# vreg.net
KiCad netlist of a schematic drawn in Altium Designer
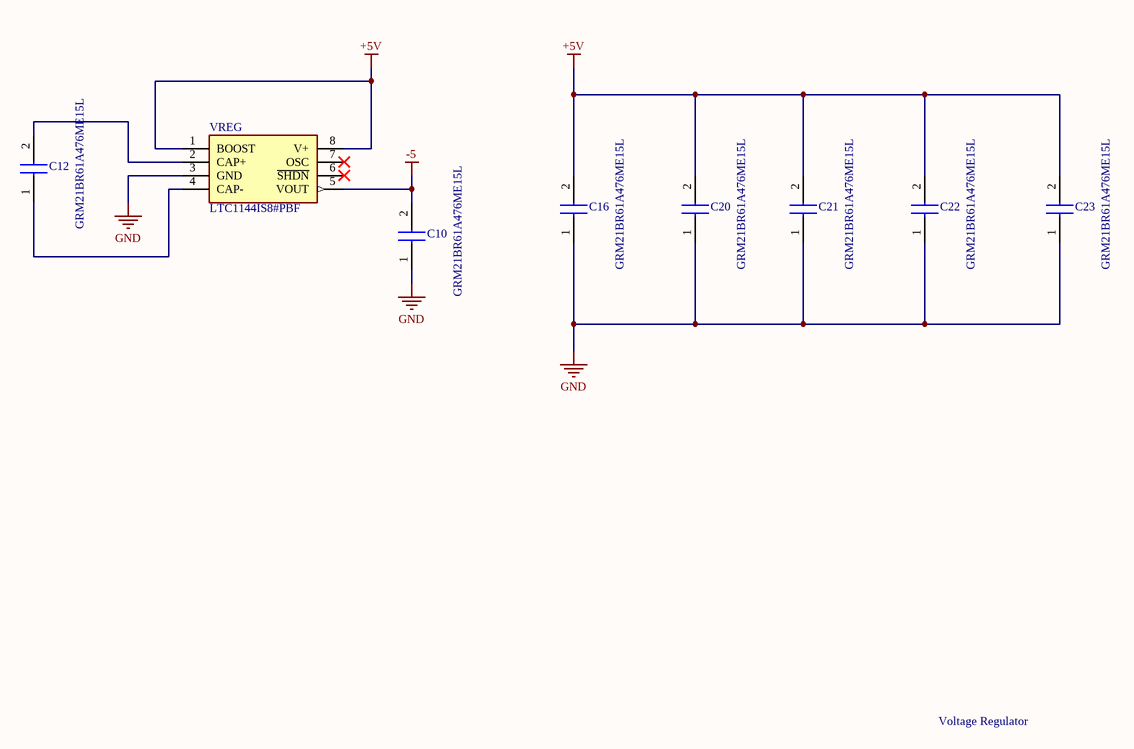
[diagram p0: vreg.SchDoc]

(export (version "E")
  (design (tool "Eeschema 10.0.6"))
  (components
    (comp (ref "C10")
      (value "GRM21BR61A476ME15L")
      (footprint "SamacSys:CAPC2012X145N")
      (description "Capacitor")
      (fields (field (name "MOUSER PART NUMBER") "81-GRM21BR61A476ME5L"))
      (libsource (lib "*") (part "GRM21BR61A476ME15L"))
    )
    (comp (ref "C12")
      (value "GRM21BR61A476ME15L")
      (footprint "SamacSys:CAPC2012X145N")
      (description "Capacitor")
      (fields (field (name "MOUSER PART NUMBER") "81-GRM21BR61A476ME5L"))
      (libsource (lib "*") (part "GRM21BR61A476ME15L"))
    )
    (comp (ref "C16")
      (value "GRM21BR61A476ME15L")
      (footprint "SamacSys:CAPC2012X145N")
      (description "Capacitor")
      (fields (field (name "MOUSER PART NUMBER") "81-GRM21BR61A476ME5L"))
      (libsource (lib "*") (part "GRM21BR61A476ME15L"))
    )
    (comp (ref "C20")
      (value "GRM21BR61A476ME15L")
      (footprint "SamacSys:CAPC2012X145N")
      (description "Capacitor")
      (fields (field (name "MOUSER PART NUMBER") "81-GRM21BR61A476ME5L"))
      (libsource (lib "*") (part "GRM21BR61A476ME15L"))
    )
    (comp (ref "C21")
      (value "GRM21BR61A476ME15L")
      (footprint "SamacSys:CAPC2012X145N")
      (description "Capacitor")
      (fields (field (name "MOUSER PART NUMBER") "81-GRM21BR61A476ME5L"))
      (libsource (lib "*") (part "GRM21BR61A476ME15L"))
    )
    (comp (ref "C22")
      (value "GRM21BR61A476ME15L")
      (footprint "SamacSys:CAPC2012X145N")
      (description "Capacitor")
      (fields (field (name "MOUSER PART NUMBER") "81-GRM21BR61A476ME5L"))
      (libsource (lib "*") (part "GRM21BR61A476ME15L"))
    )
    (comp (ref "C23")
      (value "GRM21BR61A476ME15L")
      (footprint "SamacSys:CAPC2012X145N")
      (description "Capacitor")
      (fields (field (name "MOUSER PART NUMBER") "81-GRM21BR61A476ME5L"))
      (libsource (lib "*") (part "GRM21BR61A476ME15L"))
    )
    (comp (ref "VREG")
      (value "LTC1144IS8#PBF")
      (footprint "SamacSys:SOIC127P599X175-8N")
      (description "Integrated Circuit")
      (fields (field (name "MOUSER PART NUMBER") "584-LTC1144IS8#PBF"))
      (libsource (lib "*") (part "LTC1144IS8#PBF"))
    )
  )
  (nets
    (net (code "1") (name "+5V") (class "Default")
      (node (ref "C16") (pin "2") (pinfunction "2_2") (pintype "passive"))
      (node (ref "C20") (pin "2") (pinfunction "2_2") (pintype "passive"))
      (node (ref "C21") (pin "2") (pinfunction "2_2") (pintype "passive"))
      (node (ref "C22") (pin "2") (pinfunction "2_2") (pintype "passive"))
      (node (ref "C23") (pin "2") (pinfunction "2_2") (pintype "passive"))
      (node (ref "VREG") (pin "1") (pinfunction "BOOST_1") (pintype "passive"))
      (node (ref "VREG") (pin "8") (pinfunction "V+_8") (pintype "passive"))
    )
    (net (code "2") (name "-5") (class "Default")
      (node (ref "C10") (pin "2") (pinfunction "2_2") (pintype "passive"))
      (node (ref "VREG") (pin "5") (pinfunction "VOUT_5") (pintype "output"))
    )
    (net (code "3") (name "GND") (class "Default")
      (node (ref "C10") (pin "1") (pinfunction "1_1") (pintype "passive"))
      (node (ref "C16") (pin "1") (pinfunction "1_1") (pintype "passive"))
      (node (ref "C20") (pin "1") (pinfunction "1_1") (pintype "passive"))
      (node (ref "C21") (pin "1") (pinfunction "1_1") (pintype "passive"))
      (node (ref "C22") (pin "1") (pinfunction "1_1") (pintype "passive"))
      (node (ref "C23") (pin "1") (pinfunction "1_1") (pintype "passive"))
      (node (ref "VREG") (pin "3") (pinfunction "GND_3") (pintype "power_in"))
    )
    (net (code "4") (name "Net-(VREG-CAP+)") (class "Default")
      (node (ref "C12") (pin "2") (pinfunction "2_2") (pintype "passive"))
      (node (ref "VREG") (pin "2") (pinfunction "CAP+_2") (pintype "passive"))
    )
    (net (code "5") (name "Net-(VREG-CAP-)") (class "Default")
      (node (ref "C12") (pin "1") (pinfunction "1_1") (pintype "passive"))
      (node (ref "VREG") (pin "4") (pinfunction "CAP-_4") (pintype "passive"))
    )
    (net (code "6") (name "unconnected-(VREG-OSC-Pad7)") (class "Default")
      (node (ref "VREG") (pin "7") (pinfunction "OSC_7") (pintype "passive+no_connect"))
    )
    (net (code "7") (name "unconnected-(VREG-~{SHDN}-Pad6)") (class "Default")
      (node (ref "VREG") (pin "6") (pinfunction "~{SHDN}_6") (pintype "passive+no_connect"))
    )
  )
)
